# design.net
KiCad netlist of a schematic drawn in EasyEDA Pro
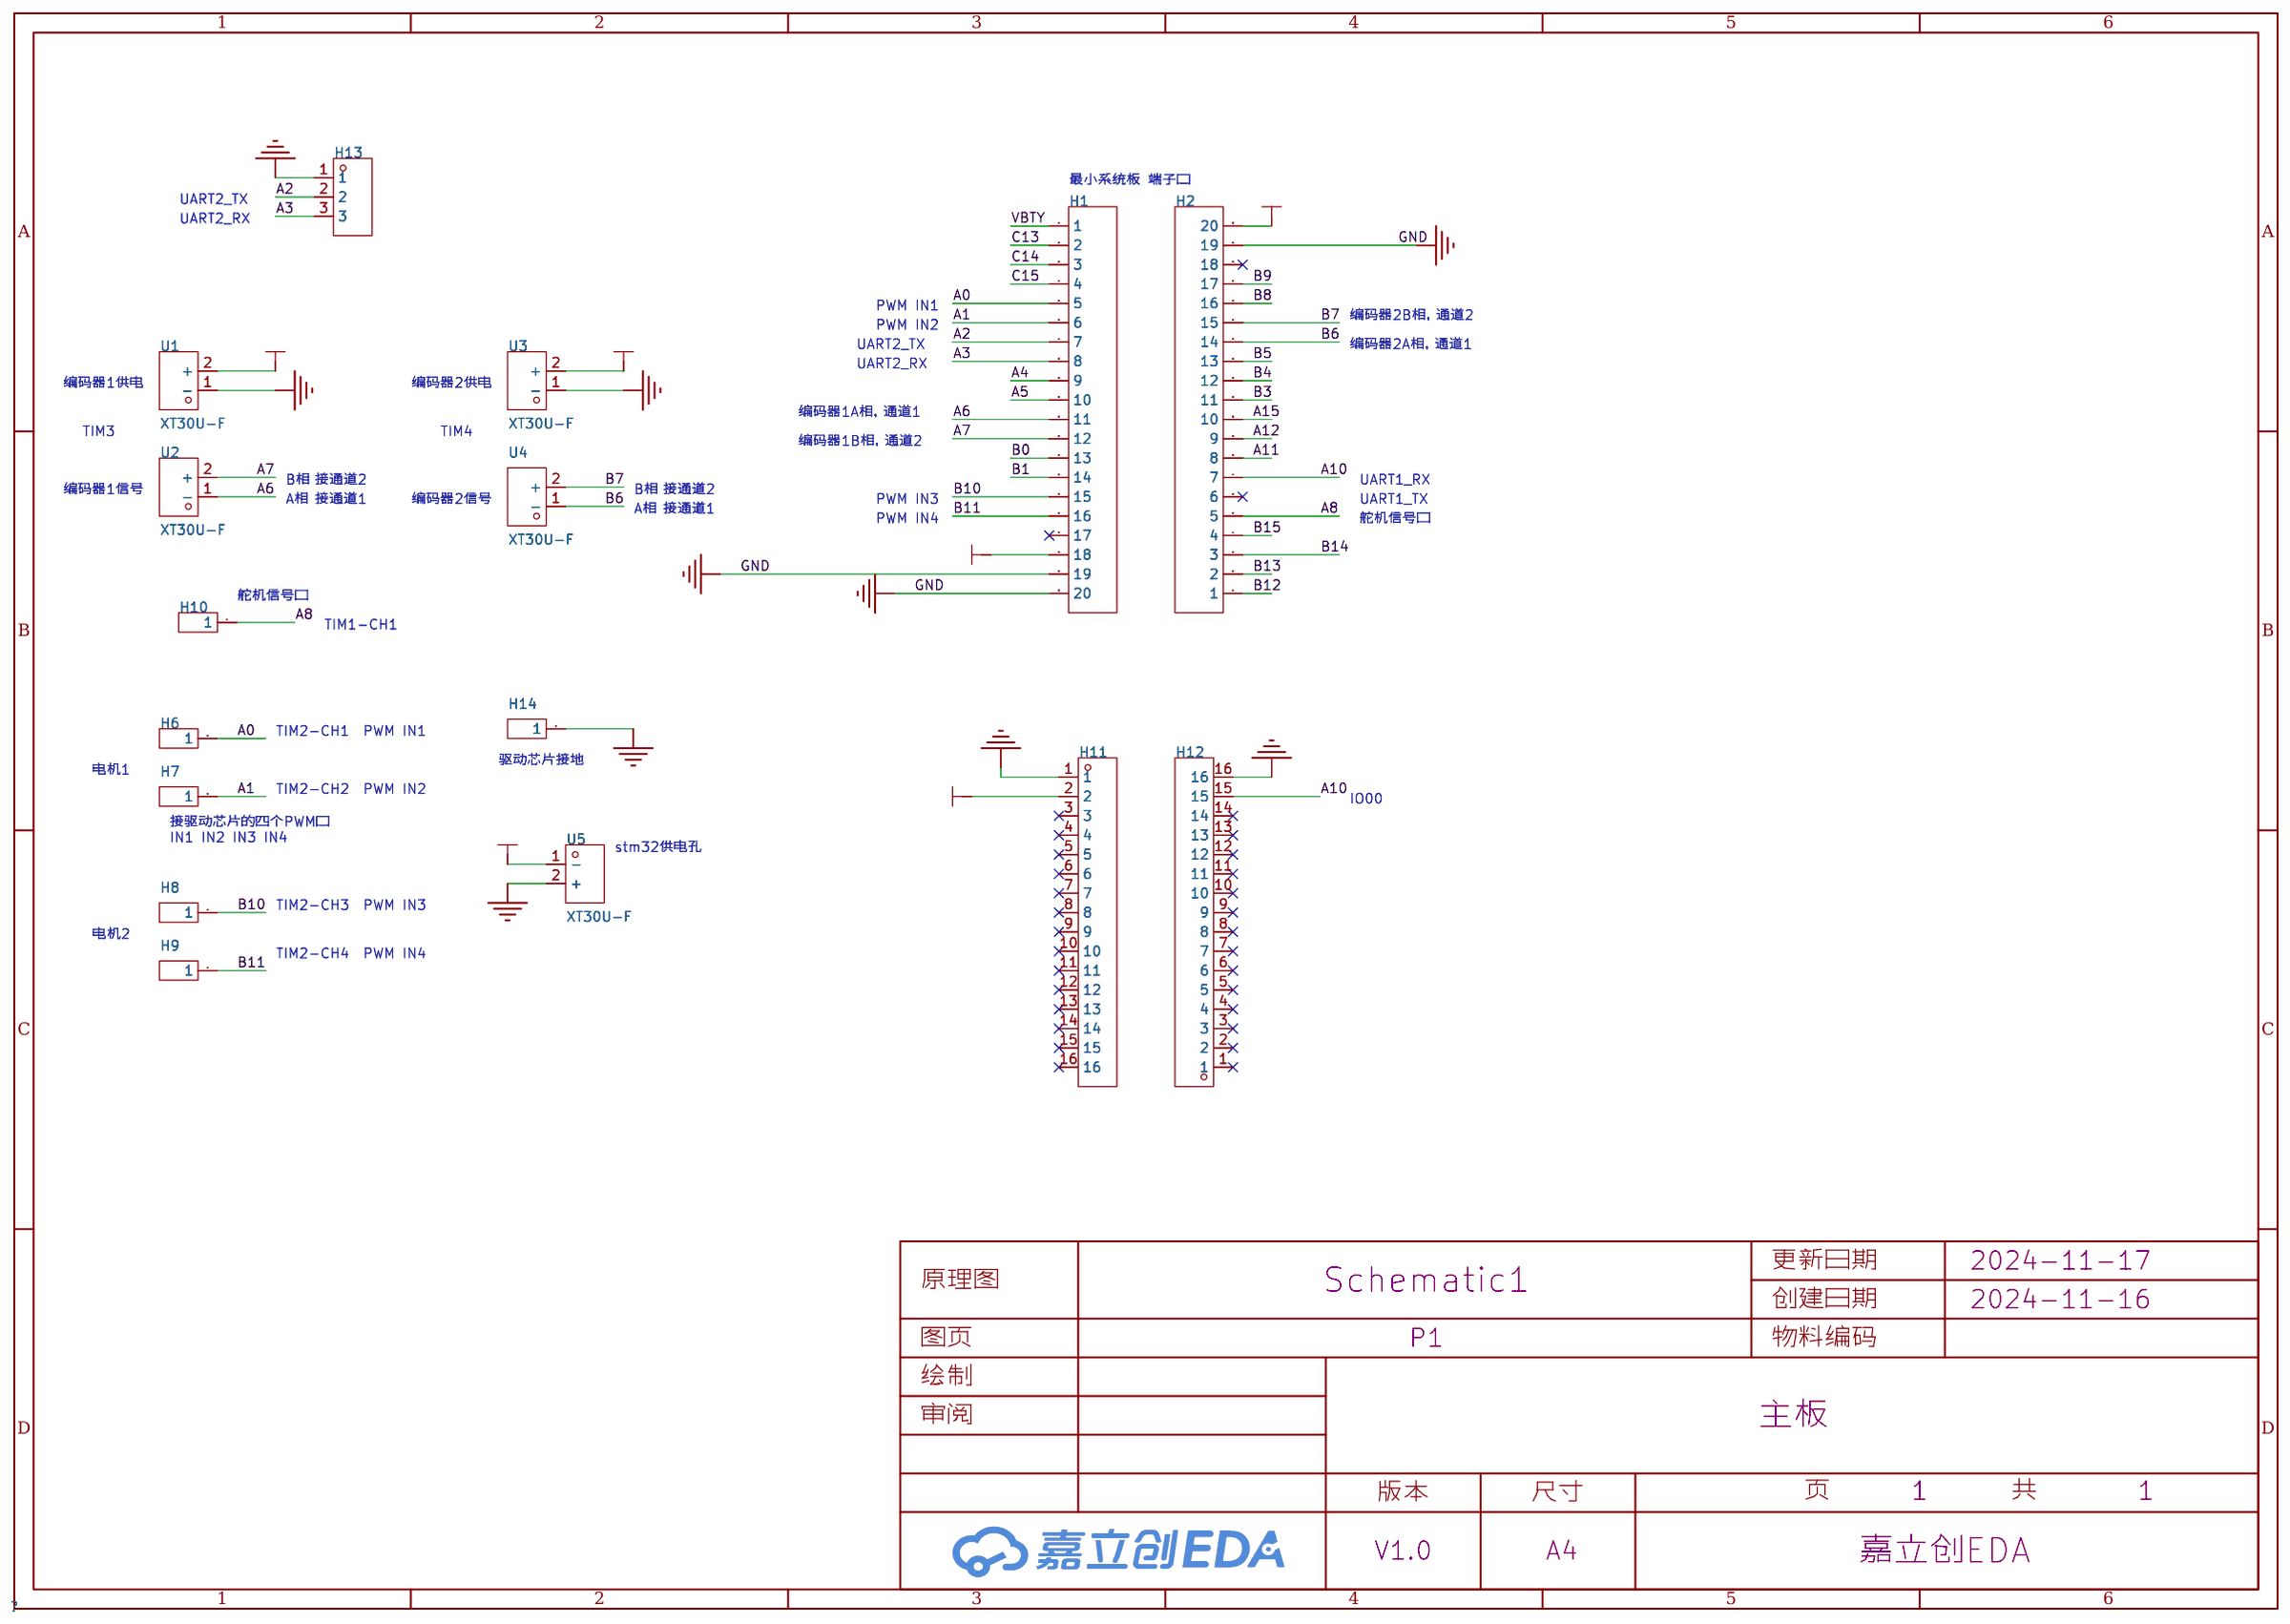
[diagram p0: schematic sheet]

(export (version "E")
  (design (tool "Eeschema 10.0.6"))
  (components
    (comp (ref "H1")
      (value "~")
      (footprint "easyedapro:HDR-TH_20P-P2.54-V-F")
      (libsource (lib "easyedapro") (part "HDR-F_2.54_1x20P"))
    )
    (comp (ref "H2")
      (value "~")
      (footprint "easyedapro:HDR-TH_20P-P2.54-V-F")
      (libsource (lib "easyedapro") (part "HDR-F_2.54_1x20P"))
    )
    (comp (ref "H6")
      (value "~")
      (footprint "easyedapro:HDR-TH_1P-V-M_XKB_X4611WV-01I-C28D40")
      (libsource (lib "easyedapro") (part "HDR_1x1"))
    )
    (comp (ref "H7")
      (value "~")
      (footprint "easyedapro:HDR-TH_1P-V-M_XKB_X4611WV-01I-C28D40")
      (libsource (lib "easyedapro") (part "HDR_1x1"))
    )
    (comp (ref "H8")
      (value "~")
      (footprint "easyedapro:HDR-TH_1P-V-M_XKB_X4611WV-01I-C28D40")
      (libsource (lib "easyedapro") (part "HDR_1x1"))
    )
    (comp (ref "H9")
      (value "~")
      (footprint "easyedapro:HDR-TH_1P-V-M_XKB_X4611WV-01I-C28D40")
      (libsource (lib "easyedapro") (part "HDR_1x1"))
    )
    (comp (ref "H10")
      (value "~")
      (footprint "easyedapro:HDR-TH_1P-V-M_XKB_X4611WV-01I-C28D40")
      (libsource (lib "easyedapro") (part "HDR_1x1"))
    )
    (comp (ref "H11")
      (value "~")
      (footprint "easyedapro:HDR-TH_16P-P2.54-V-F")
      (libsource (lib "easyedapro") (part "HDR-F_2.54_1x16P"))
    )
    (comp (ref "H12")
      (value "~")
      (footprint "easyedapro:HDR-TH_16P-P2.54-V-F")
      (libsource (lib "easyedapro") (part "HDR-F_2.54_1x16P"))
    )
    (comp (ref "H13")
      (value "~")
      (footprint "easyedapro:HDR-TH_3P-P2.54-V-F")
      (libsource (lib "easyedapro") (part "PM254V-11-03-H85"))
    )
    (comp (ref "H14")
      (value "~")
      (footprint "easyedapro:HDR-TH_1P-V-M_XKB_X4611WV-01I-C28D40")
      (libsource (lib "easyedapro") (part "HDR_1x1"))
    )
    (comp (ref "U1")
      (value "XT30U-F")
      (footprint "easyedapro:CONN-TH_XT30U-F")
      (description "类别:-;类型1:-;")
      (fields (field (name "Manufacturer") "AMASS(艾迈斯)"))
      (libsource (lib "easyedapro") (part "XT30U-F"))
    )
    (comp (ref "U2")
      (value "XT30U-F")
      (footprint "easyedapro:CONN-TH_XT30U-F")
      (description "类别:-;类型1:-;")
      (fields (field (name "Manufacturer") "AMASS(艾迈斯)"))
      (libsource (lib "easyedapro") (part "XT30U-F"))
    )
    (comp (ref "U3")
      (value "XT30U-F")
      (footprint "easyedapro:CONN-TH_XT30U-F")
      (description "类别:-;类型1:-;")
      (fields (field (name "Manufacturer") "AMASS(艾迈斯)"))
      (libsource (lib "easyedapro") (part "XT30U-F"))
    )
    (comp (ref "U4")
      (value "XT30U-F")
      (footprint "easyedapro:CONN-TH_XT30U-F")
      (description "类别:-;类型1:-;")
      (fields (field (name "Manufacturer") "AMASS(艾迈斯)"))
      (libsource (lib "easyedapro") (part "XT30U-F"))
    )
    (comp (ref "U5")
      (value "XT30U-F")
      (footprint "easyedapro:CONN-TH_XT30U-F")
      (description "类别:-;类型1:-;")
      (fields (field (name "Manufacturer") "AMASS(艾迈斯)"))
      (libsource (lib "easyedapro") (part "XT30U-F"))
    )
  )
  (nets
    (net (code "1") (name "/A0") (class "Default")
      (node (ref "H1") (pin "5") (pinfunction "5_5") (pintype "input"))
      (node (ref "H6") (pin "1") (pinfunction "1_1") (pintype "unspecified"))
    )
    (net (code "2") (name "/A1") (class "Default")
      (node (ref "H1") (pin "6") (pinfunction "6_6") (pintype "input"))
      (node (ref "H7") (pin "1") (pinfunction "1_1") (pintype "unspecified"))
    )
    (net (code "3") (name "/A2") (class "Default")
      (node (ref "H1") (pin "7") (pinfunction "7_7") (pintype "input"))
      (node (ref "H13") (pin "2") (pinfunction "2_2") (pintype "unspecified"))
    )
    (net (code "4") (name "/A3") (class "Default")
      (node (ref "H1") (pin "8") (pinfunction "8_8") (pintype "input"))
      (node (ref "H13") (pin "3") (pinfunction "3_3") (pintype "unspecified"))
    )
    (net (code "5") (name "/A4") (class "Default")
      (node (ref "H1") (pin "9") (pinfunction "9_9") (pintype "input"))
    )
    (net (code "6") (name "/A5") (class "Default")
      (node (ref "H1") (pin "10") (pinfunction "10_10") (pintype "input"))
    )
    (net (code "7") (name "/A6") (class "Default")
      (node (ref "H1") (pin "11") (pinfunction "11_11") (pintype "input"))
      (node (ref "U2") (pin "1") (pinfunction "-_1") (pintype "unspecified"))
    )
    (net (code "8") (name "/A7") (class "Default")
      (node (ref "H1") (pin "12") (pinfunction "12_12") (pintype "input"))
      (node (ref "U2") (pin "2") (pinfunction "+_2") (pintype "unspecified"))
    )
    (net (code "9") (name "/A8") (class "Default")
      (node (ref "H10") (pin "1") (pinfunction "1_1") (pintype "unspecified"))
      (node (ref "H2") (pin "5") (pinfunction "5_5") (pintype "input"))
    )
    (net (code "10") (name "/A10") (class "Default")
      (node (ref "H12") (pin "15") (pinfunction "15_15") (pintype "input"))
      (node (ref "H2") (pin "7") (pinfunction "7_7") (pintype "input"))
    )
    (net (code "11") (name "/A11") (class "Default")
      (node (ref "H2") (pin "8") (pinfunction "8_8") (pintype "input"))
    )
    (net (code "12") (name "/A12") (class "Default")
      (node (ref "H2") (pin "9") (pinfunction "9_9") (pintype "input"))
    )
    (net (code "13") (name "/A15") (class "Default")
      (node (ref "H2") (pin "10") (pinfunction "10_10") (pintype "input"))
    )
    (net (code "14") (name "/B0") (class "Default")
      (node (ref "H1") (pin "13") (pinfunction "13_13") (pintype "input"))
    )
    (net (code "15") (name "/B1") (class "Default")
      (node (ref "H1") (pin "14") (pinfunction "14_14") (pintype "input"))
    )
    (net (code "16") (name "/B3") (class "Default")
      (node (ref "H2") (pin "11") (pinfunction "11_11") (pintype "input"))
    )
    (net (code "17") (name "/B4") (class "Default")
      (node (ref "H2") (pin "12") (pinfunction "12_12") (pintype "input"))
    )
    (net (code "18") (name "/B5") (class "Default")
      (node (ref "H2") (pin "13") (pinfunction "13_13") (pintype "input"))
    )
    (net (code "19") (name "/B6") (class "Default")
      (node (ref "H2") (pin "14") (pinfunction "14_14") (pintype "input"))
      (node (ref "U4") (pin "1") (pinfunction "-_1") (pintype "unspecified"))
    )
    (net (code "20") (name "/B7") (class "Default")
      (node (ref "H2") (pin "15") (pinfunction "15_15") (pintype "input"))
      (node (ref "U4") (pin "2") (pinfunction "+_2") (pintype "unspecified"))
    )
    (net (code "21") (name "/B8") (class "Default")
      (node (ref "H2") (pin "16") (pinfunction "16_16") (pintype "input"))
    )
    (net (code "22") (name "/B9") (class "Default")
      (node (ref "H2") (pin "17") (pinfunction "17_17") (pintype "input"))
    )
    (net (code "23") (name "/B10") (class "Default")
      (node (ref "H1") (pin "15") (pinfunction "15_15") (pintype "input"))
      (node (ref "H8") (pin "1") (pinfunction "1_1") (pintype "unspecified"))
    )
    (net (code "24") (name "/B11") (class "Default")
      (node (ref "H1") (pin "16") (pinfunction "16_16") (pintype "input"))
      (node (ref "H9") (pin "1") (pinfunction "1_1") (pintype "unspecified"))
    )
    (net (code "25") (name "/B12") (class "Default")
      (node (ref "H2") (pin "1") (pinfunction "1_1") (pintype "input"))
    )
    (net (code "26") (name "/B13") (class "Default")
      (node (ref "H2") (pin "2") (pinfunction "2_2") (pintype "input"))
    )
    (net (code "27") (name "/B14") (class "Default")
      (node (ref "H2") (pin "3") (pinfunction "3_3") (pintype "input"))
    )
    (net (code "28") (name "/B15") (class "Default")
      (node (ref "H2") (pin "4") (pinfunction "4_4") (pintype "input"))
    )
    (net (code "29") (name "/C13") (class "Default")
      (node (ref "H1") (pin "2") (pinfunction "2_2") (pintype "input"))
    )
    (net (code "30") (name "/C14") (class "Default")
      (node (ref "H1") (pin "3") (pinfunction "3_3") (pintype "input"))
    )
    (net (code "31") (name "/C15") (class "Default")
      (node (ref "H1") (pin "4") (pinfunction "4_4") (pintype "input"))
    )
    (net (code "32") (name "/VBTY") (class "Default")
      (node (ref "H1") (pin "1") (pinfunction "1_1") (pintype "input"))
    )
    (net (code "33") (name "3V3") (class "Default")
      (node (ref "H11") (pin "2") (pinfunction "2_2") (pintype "input"))
      (node (ref "H2") (pin "20") (pinfunction "20_20") (pintype "input"))
      (node (ref "U1") (pin "2") (pinfunction "+_2") (pintype "unspecified"))
      (node (ref "U3") (pin "2") (pinfunction "+_2") (pintype "unspecified"))
    )
    (net (code "34") (name "3V31") (class "Default")
      (node (ref "H1") (pin "18") (pinfunction "18_18") (pintype "input"))
      (node (ref "U5") (pin "1") (pinfunction "-_1") (pintype "unspecified"))
    )
    (net (code "35") (name "GND") (class "Default")
      (node (ref "H1") (pin "19") (pinfunction "19_19") (pintype "input"))
      (node (ref "H1") (pin "20") (pinfunction "20_20") (pintype "input"))
      (node (ref "H11") (pin "1") (pinfunction "1_1") (pintype "input"))
      (node (ref "H12") (pin "16") (pinfunction "16_16") (pintype "input"))
      (node (ref "H13") (pin "1") (pinfunction "1_1") (pintype "unspecified"))
      (node (ref "H14") (pin "1") (pinfunction "1_1") (pintype "unspecified"))
      (node (ref "H2") (pin "19") (pinfunction "19_19") (pintype "input"))
      (node (ref "U1") (pin "1") (pinfunction "-_1") (pintype "unspecified"))
      (node (ref "U3") (pin "1") (pinfunction "-_1") (pintype "unspecified"))
      (node (ref "U5") (pin "2") (pinfunction "+_2") (pintype "unspecified"))
    )
    (net (code "36") (name "unconnected-(H1-Pad17)") (class "Default")
      (node (ref "H1") (pin "17") (pinfunction "17_17") (pintype "input+no_connect"))
    )
    (net (code "37") (name "unconnected-(H2-Pad6)") (class "Default")
      (node (ref "H2") (pin "6") (pinfunction "6_6") (pintype "input+no_connect"))
    )
    (net (code "38") (name "unconnected-(H2-Pad18)") (class "Default")
      (node (ref "H2") (pin "18") (pinfunction "18_18") (pintype "input+no_connect"))
    )
    (net (code "39") (name "unconnected-(H11-Pad3)") (class "Default")
      (node (ref "H11") (pin "3") (pinfunction "3_3") (pintype "input+no_connect"))
    )
    (net (code "40") (name "unconnected-(H11-Pad4)") (class "Default")
      (node (ref "H11") (pin "4") (pinfunction "4_4") (pintype "input+no_connect"))
    )
    (net (code "41") (name "unconnected-(H11-Pad5)") (class "Default")
      (node (ref "H11") (pin "5") (pinfunction "5_5") (pintype "input+no_connect"))
    )
    (net (code "42") (name "unconnected-(H11-Pad6)") (class "Default")
      (node (ref "H11") (pin "6") (pinfunction "6_6") (pintype "input+no_connect"))
    )
    (net (code "43") (name "unconnected-(H11-Pad7)") (class "Default")
      (node (ref "H11") (pin "7") (pinfunction "7_7") (pintype "input+no_connect"))
    )
    (net (code "44") (name "unconnected-(H11-Pad8)") (class "Default")
      (node (ref "H11") (pin "8") (pinfunction "8_8") (pintype "input+no_connect"))
    )
    (net (code "45") (name "unconnected-(H11-Pad9)") (class "Default")
      (node (ref "H11") (pin "9") (pinfunction "9_9") (pintype "input+no_connect"))
    )
    (net (code "46") (name "unconnected-(H11-Pad10)") (class "Default")
      (node (ref "H11") (pin "10") (pinfunction "10_10") (pintype "input+no_connect"))
    )
    (net (code "47") (name "unconnected-(H11-Pad11)") (class "Default")
      (node (ref "H11") (pin "11") (pinfunction "11_11") (pintype "input+no_connect"))
    )
    (net (code "48") (name "unconnected-(H11-Pad12)") (class "Default")
      (node (ref "H11") (pin "12") (pinfunction "12_12") (pintype "input+no_connect"))
    )
    (net (code "49") (name "unconnected-(H11-Pad13)") (class "Default")
      (node (ref "H11") (pin "13") (pinfunction "13_13") (pintype "input+no_connect"))
    )
    (net (code "50") (name "unconnected-(H11-Pad14)") (class "Default")
      (node (ref "H11") (pin "14") (pinfunction "14_14") (pintype "input+no_connect"))
    )
    (net (code "51") (name "unconnected-(H11-Pad15)") (class "Default")
      (node (ref "H11") (pin "15") (pinfunction "15_15") (pintype "input+no_connect"))
    )
    (net (code "52") (name "unconnected-(H11-Pad16)") (class "Default")
      (node (ref "H11") (pin "16") (pinfunction "16_16") (pintype "input+no_connect"))
    )
    (net (code "53") (name "unconnected-(H12-Pad1)") (class "Default")
      (node (ref "H12") (pin "1") (pinfunction "1_1") (pintype "input+no_connect"))
    )
    (net (code "54") (name "unconnected-(H12-Pad2)") (class "Default")
      (node (ref "H12") (pin "2") (pinfunction "2_2") (pintype "input+no_connect"))
    )
    (net (code "55") (name "unconnected-(H12-Pad3)") (class "Default")
      (node (ref "H12") (pin "3") (pinfunction "3_3") (pintype "input+no_connect"))
    )
    (net (code "56") (name "unconnected-(H12-Pad4)") (class "Default")
      (node (ref "H12") (pin "4") (pinfunction "4_4") (pintype "input+no_connect"))
    )
    (net (code "57") (name "unconnected-(H12-Pad5)") (class "Default")
      (node (ref "H12") (pin "5") (pinfunction "5_5") (pintype "input+no_connect"))
    )
    (net (code "58") (name "unconnected-(H12-Pad6)") (class "Default")
      (node (ref "H12") (pin "6") (pinfunction "6_6") (pintype "input+no_connect"))
    )
    (net (code "59") (name "unconnected-(H12-Pad7)") (class "Default")
      (node (ref "H12") (pin "7") (pinfunction "7_7") (pintype "input+no_connect"))
    )
    (net (code "60") (name "unconnected-(H12-Pad8)") (class "Default")
      (node (ref "H12") (pin "8") (pinfunction "8_8") (pintype "input+no_connect"))
    )
    (net (code "61") (name "unconnected-(H12-Pad9)") (class "Default")
      (node (ref "H12") (pin "9") (pinfunction "9_9") (pintype "input+no_connect"))
    )
    (net (code "62") (name "unconnected-(H12-Pad10)") (class "Default")
      (node (ref "H12") (pin "10") (pinfunction "10_10") (pintype "input+no_connect"))
    )
    (net (code "63") (name "unconnected-(H12-Pad11)") (class "Default")
      (node (ref "H12") (pin "11") (pinfunction "11_11") (pintype "input+no_connect"))
    )
    (net (code "64") (name "unconnected-(H12-Pad12)") (class "Default")
      (node (ref "H12") (pin "12") (pinfunction "12_12") (pintype "input+no_connect"))
    )
    (net (code "65") (name "unconnected-(H12-Pad13)") (class "Default")
      (node (ref "H12") (pin "13") (pinfunction "13_13") (pintype "input+no_connect"))
    )
    (net (code "66") (name "unconnected-(H12-Pad14)") (class "Default")
      (node (ref "H12") (pin "14") (pinfunction "14_14") (pintype "input+no_connect"))
    )
  )
)
